# Power_Middle.net
KiCad netlist of a schematic drawn in Altium Designer
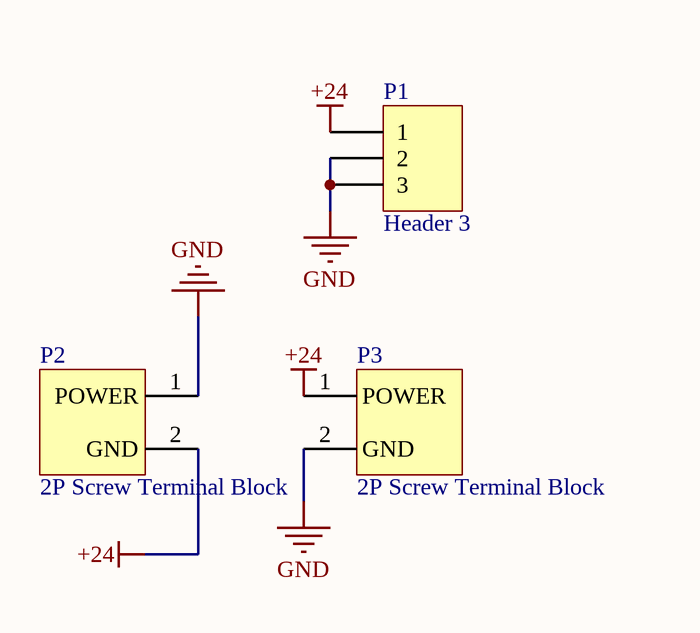
[diagram p0: Power_Middle.SchDoc]

(export (version "E")
  (design (tool "Eeschema 10.0.6"))
  (components
    (comp (ref "P1")
      (value "Header 3")
      (footprint "HDR1X3")
      (description "Header, 3-Pin")
      (fields (field (name "PUBLISHER") "Altium Limited"))
      (libsource (lib "Miscellaneous Connectors") (part "Header 3"))
    )
    (comp (ref "P2")
      (value "2P Screw Terminal Block")
      (footprint "P_Terminal block 3.5mm-pitch")
      (description "Green Straight pin 3.5mm  pitch; P=3.5mm  Screw terminal ROHS")
      (fields (field (name "MFR PART #") "KF350-3.5-2P") (field (name "MANUFACTURER") "Cixi Kefa Elec"))
      (libsource (lib "ECEN5730Lib_2023_05_DS") (part "P_Terminal block"))
    )
    (comp (ref "P3")
      (value "2P Screw Terminal Block")
      (footprint "P_Terminal block 3.5mm-pitch")
      (description "Green Straight pin 3.5mm  pitch; P=3.5mm  Screw terminal ROHS")
      (fields (field (name "MFR PART #") "KF350-3.5-2P") (field (name "MANUFACTURER") "Cixi Kefa Elec"))
      (libsource (lib "") (part "P_Terminal block_1"))
    )
  )
  (nets
    (net (code "1") (name "+24") (class "Default")
      (node (ref "P1") (pin "1") (pinfunction "1_1") (pintype "passive"))
      (node (ref "P2") (pin "2") (pinfunction "GND_2") (pintype "passive"))
      (node (ref "P3") (pin "1") (pinfunction "POWER_1") (pintype "passive"))
    )
    (net (code "2") (name "GND") (class "Default")
      (node (ref "P1") (pin "2") (pinfunction "2_2") (pintype "passive"))
      (node (ref "P1") (pin "3") (pinfunction "3_3") (pintype "passive"))
      (node (ref "P2") (pin "1") (pinfunction "POWER_1") (pintype "passive"))
      (node (ref "P3") (pin "2") (pinfunction "GND_2") (pintype "passive"))
    )
  )
)
